# mxboard.net
KiCad netlist of a schematic drawn in EAGLE
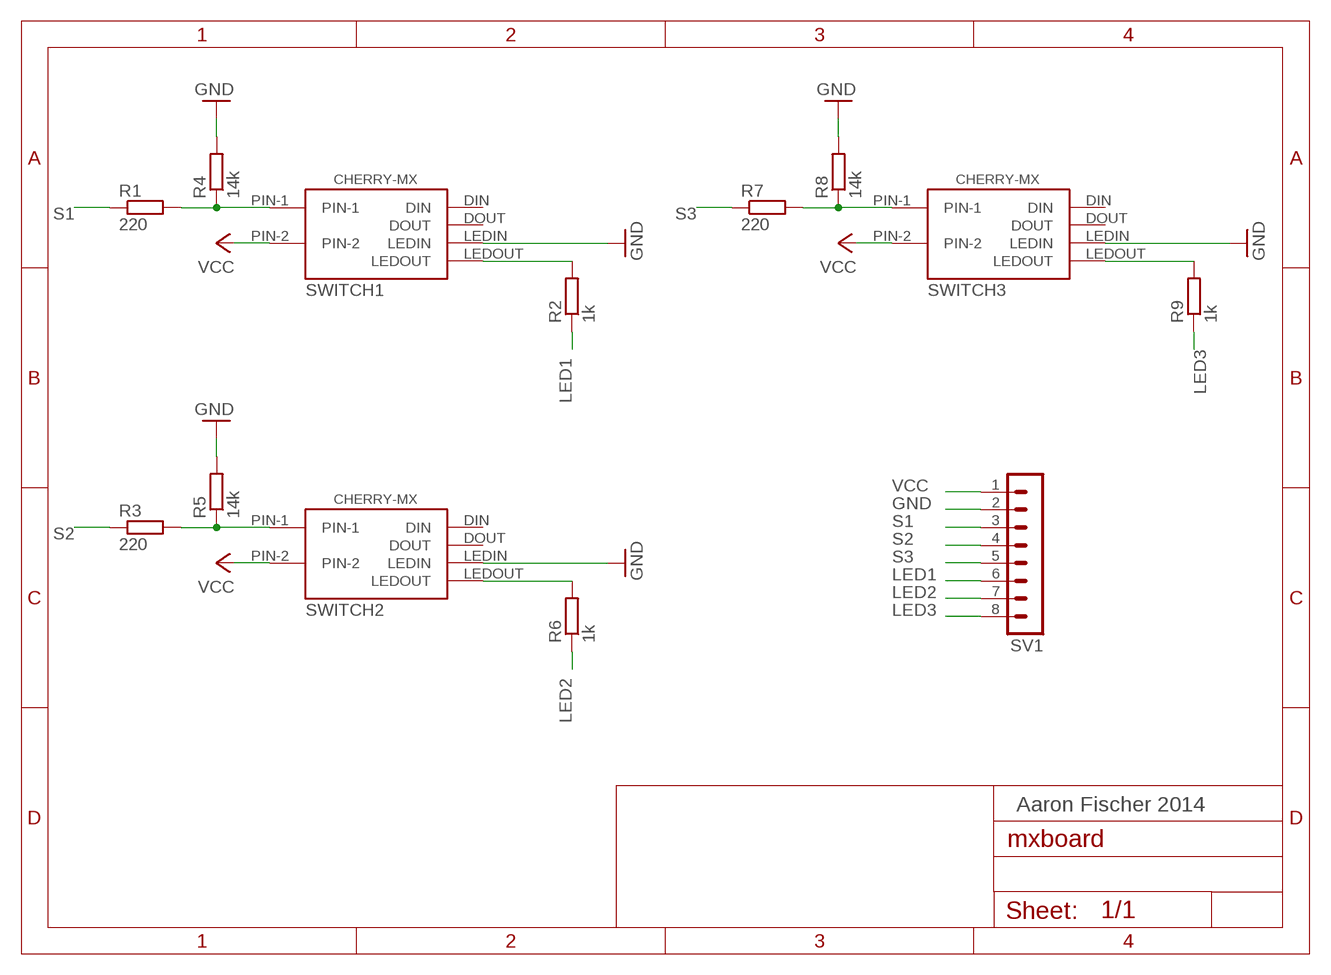
[diagram p0: schematic, sheet 1]

(export (version "E")
  (design (tool "Eeschema 10.0.6"))
  (components
    (comp (ref "R1")
      (value "220")
      (footprint "eagle-import:R0805")
      (libsource (lib "eagle-import") (part "R-EU_R0805"))
    )
    (comp (ref "R2")
      (value "1k")
      (footprint "eagle-import:R0805")
      (libsource (lib "eagle-import") (part "R-EU_R0805"))
    )
    (comp (ref "R3")
      (value "220")
      (footprint "eagle-import:R0805")
      (libsource (lib "eagle-import") (part "R-EU_R0805"))
    )
    (comp (ref "R4")
      (value "14k")
      (footprint "eagle-import:R0805")
      (libsource (lib "eagle-import") (part "R-EU_R0805"))
    )
    (comp (ref "R5")
      (value "14k")
      (footprint "eagle-import:R0805")
      (libsource (lib "eagle-import") (part "R-EU_R0805"))
    )
    (comp (ref "R6")
      (value "1k")
      (footprint "eagle-import:R0805")
      (libsource (lib "eagle-import") (part "R-EU_R0805"))
    )
    (comp (ref "R7")
      (value "220")
      (footprint "eagle-import:R0805")
      (libsource (lib "eagle-import") (part "R-EU_R0805"))
    )
    (comp (ref "R8")
      (value "14k")
      (footprint "eagle-import:R0805")
      (libsource (lib "eagle-import") (part "R-EU_R0805"))
    )
    (comp (ref "R9")
      (value "1k")
      (footprint "eagle-import:R0805")
      (libsource (lib "eagle-import") (part "R-EU_R0805"))
    )
    (comp (ref "SV1")
      (value "MA08-1")
      (footprint "eagle-import:MA08-1")
      (libsource (lib "eagle-import") (part "MA08-1"))
    )
    (comp (ref "SWITCH1")
      (value "CHERRY-MX-I")
      (footprint "eagle-import:CHERRY-MX-I")
      (libsource (lib "eagle-import") (part "CHERRY-MX-I"))
    )
    (comp (ref "SWITCH2")
      (value "CHERRY-MX-I")
      (footprint "eagle-import:CHERRY-MX-I")
      (libsource (lib "eagle-import") (part "CHERRY-MX-I"))
    )
    (comp (ref "SWITCH3")
      (value "CHERRY-MX-I")
      (footprint "eagle-import:CHERRY-MX-I")
      (libsource (lib "eagle-import") (part "CHERRY-MX-I"))
    )
  )
  (nets
    (net (code "1") (name "/LED1") (class "Default")
      (node (ref "R2") (pin "1") (pinfunction "1_1") (pintype "passive"))
      (node (ref "SV1") (pin "6") (pinfunction "6_6") (pintype "passive"))
    )
    (net (code "2") (name "/LED2") (class "Default")
      (node (ref "R6") (pin "1") (pinfunction "1_1") (pintype "passive"))
      (node (ref "SV1") (pin "7") (pinfunction "7_7") (pintype "passive"))
    )
    (net (code "3") (name "/LED3") (class "Default")
      (node (ref "R9") (pin "1") (pinfunction "1_1") (pintype "passive"))
      (node (ref "SV1") (pin "8") (pinfunction "8_8") (pintype "passive"))
    )
    (net (code "4") (name "/S1") (class "Default")
      (node (ref "R1") (pin "1") (pinfunction "1_1") (pintype "passive"))
      (node (ref "SV1") (pin "3") (pinfunction "3_3") (pintype "passive"))
    )
    (net (code "5") (name "/S2") (class "Default")
      (node (ref "R3") (pin "1") (pinfunction "1_1") (pintype "passive"))
      (node (ref "SV1") (pin "4") (pinfunction "4_4") (pintype "passive"))
    )
    (net (code "6") (name "/S3") (class "Default")
      (node (ref "R7") (pin "1") (pinfunction "1_1") (pintype "passive"))
      (node (ref "SV1") (pin "5") (pinfunction "5_5") (pintype "passive"))
    )
    (net (code "7") (name "GND") (class "Default")
      (node (ref "R4") (pin "2") (pinfunction "2_2") (pintype "passive"))
      (node (ref "R5") (pin "2") (pinfunction "2_2") (pintype "passive"))
      (node (ref "R8") (pin "2") (pinfunction "2_2") (pintype "passive"))
      (node (ref "SV1") (pin "2") (pinfunction "2_2") (pintype "passive"))
      (node (ref "SWITCH1") (pin "LEDIN") (pinfunction "LEDIN_LEDIN") (pintype "bidirectional"))
      (node (ref "SWITCH2") (pin "LEDIN") (pinfunction "LEDIN_LEDIN") (pintype "bidirectional"))
      (node (ref "SWITCH3") (pin "LEDIN") (pinfunction "LEDIN_LEDIN") (pintype "bidirectional"))
    )
    (net (code "8") (name "Net-(R1-Pad2)") (class "Default")
      (node (ref "R1") (pin "2") (pinfunction "2_2") (pintype "passive"))
      (node (ref "R4") (pin "1") (pinfunction "1_1") (pintype "passive"))
      (node (ref "SWITCH1") (pin "PIN-1") (pinfunction "PIN-1_PIN-1") (pintype "bidirectional"))
    )
    (net (code "9") (name "Net-(R2-Pad2)") (class "Default")
      (node (ref "R2") (pin "2") (pinfunction "2_2") (pintype "passive"))
      (node (ref "SWITCH1") (pin "LEDOUT") (pinfunction "LEDOUT_LEDOUT") (pintype "bidirectional"))
    )
    (net (code "10") (name "Net-(R3-Pad2)") (class "Default")
      (node (ref "R3") (pin "2") (pinfunction "2_2") (pintype "passive"))
      (node (ref "R5") (pin "1") (pinfunction "1_1") (pintype "passive"))
      (node (ref "SWITCH2") (pin "PIN-1") (pinfunction "PIN-1_PIN-1") (pintype "bidirectional"))
    )
    (net (code "11") (name "Net-(R6-Pad2)") (class "Default")
      (node (ref "R6") (pin "2") (pinfunction "2_2") (pintype "passive"))
      (node (ref "SWITCH2") (pin "LEDOUT") (pinfunction "LEDOUT_LEDOUT") (pintype "bidirectional"))
    )
    (net (code "12") (name "Net-(R7-Pad2)") (class "Default")
      (node (ref "R7") (pin "2") (pinfunction "2_2") (pintype "passive"))
      (node (ref "R8") (pin "1") (pinfunction "1_1") (pintype "passive"))
      (node (ref "SWITCH3") (pin "PIN-1") (pinfunction "PIN-1_PIN-1") (pintype "bidirectional"))
    )
    (net (code "13") (name "Net-(R9-Pad2)") (class "Default")
      (node (ref "R9") (pin "2") (pinfunction "2_2") (pintype "passive"))
      (node (ref "SWITCH3") (pin "LEDOUT") (pinfunction "LEDOUT_LEDOUT") (pintype "bidirectional"))
    )
    (net (code "14") (name "VCC") (class "Default")
      (node (ref "SV1") (pin "1") (pinfunction "1_1") (pintype "passive"))
      (node (ref "SWITCH1") (pin "PIN-2") (pinfunction "PIN-2_PIN-2") (pintype "bidirectional"))
      (node (ref "SWITCH2") (pin "PIN-2") (pinfunction "PIN-2_PIN-2") (pintype "bidirectional"))
      (node (ref "SWITCH3") (pin "PIN-2") (pinfunction "PIN-2_PIN-2") (pintype "bidirectional"))
    )
    (net (code "15") (name "unconnected-(SWITCH1-PadDIN)") (class "Default")
      (node (ref "SWITCH1") (pin "DIN") (pinfunction "DIN_DIN") (pintype "bidirectional"))
    )
    (net (code "16") (name "unconnected-(SWITCH1-PadDOUT)") (class "Default")
      (node (ref "SWITCH1") (pin "DOUT") (pinfunction "DOUT_DOUT") (pintype "bidirectional"))
    )
    (net (code "17") (name "unconnected-(SWITCH2-PadDIN)") (class "Default")
      (node (ref "SWITCH2") (pin "DIN") (pinfunction "DIN_DIN") (pintype "bidirectional"))
    )
    (net (code "18") (name "unconnected-(SWITCH2-PadDOUT)") (class "Default")
      (node (ref "SWITCH2") (pin "DOUT") (pinfunction "DOUT_DOUT") (pintype "bidirectional"))
    )
    (net (code "19") (name "unconnected-(SWITCH3-PadDIN)") (class "Default")
      (node (ref "SWITCH3") (pin "DIN") (pinfunction "DIN_DIN") (pintype "bidirectional"))
    )
    (net (code "20") (name "unconnected-(SWITCH3-PadDOUT)") (class "Default")
      (node (ref "SWITCH3") (pin "DOUT") (pinfunction "DOUT_DOUT") (pintype "bidirectional"))
    )
  )
)
